# touch-24-v4.net
KiCad netlist of a schematic drawn in Altium Designer
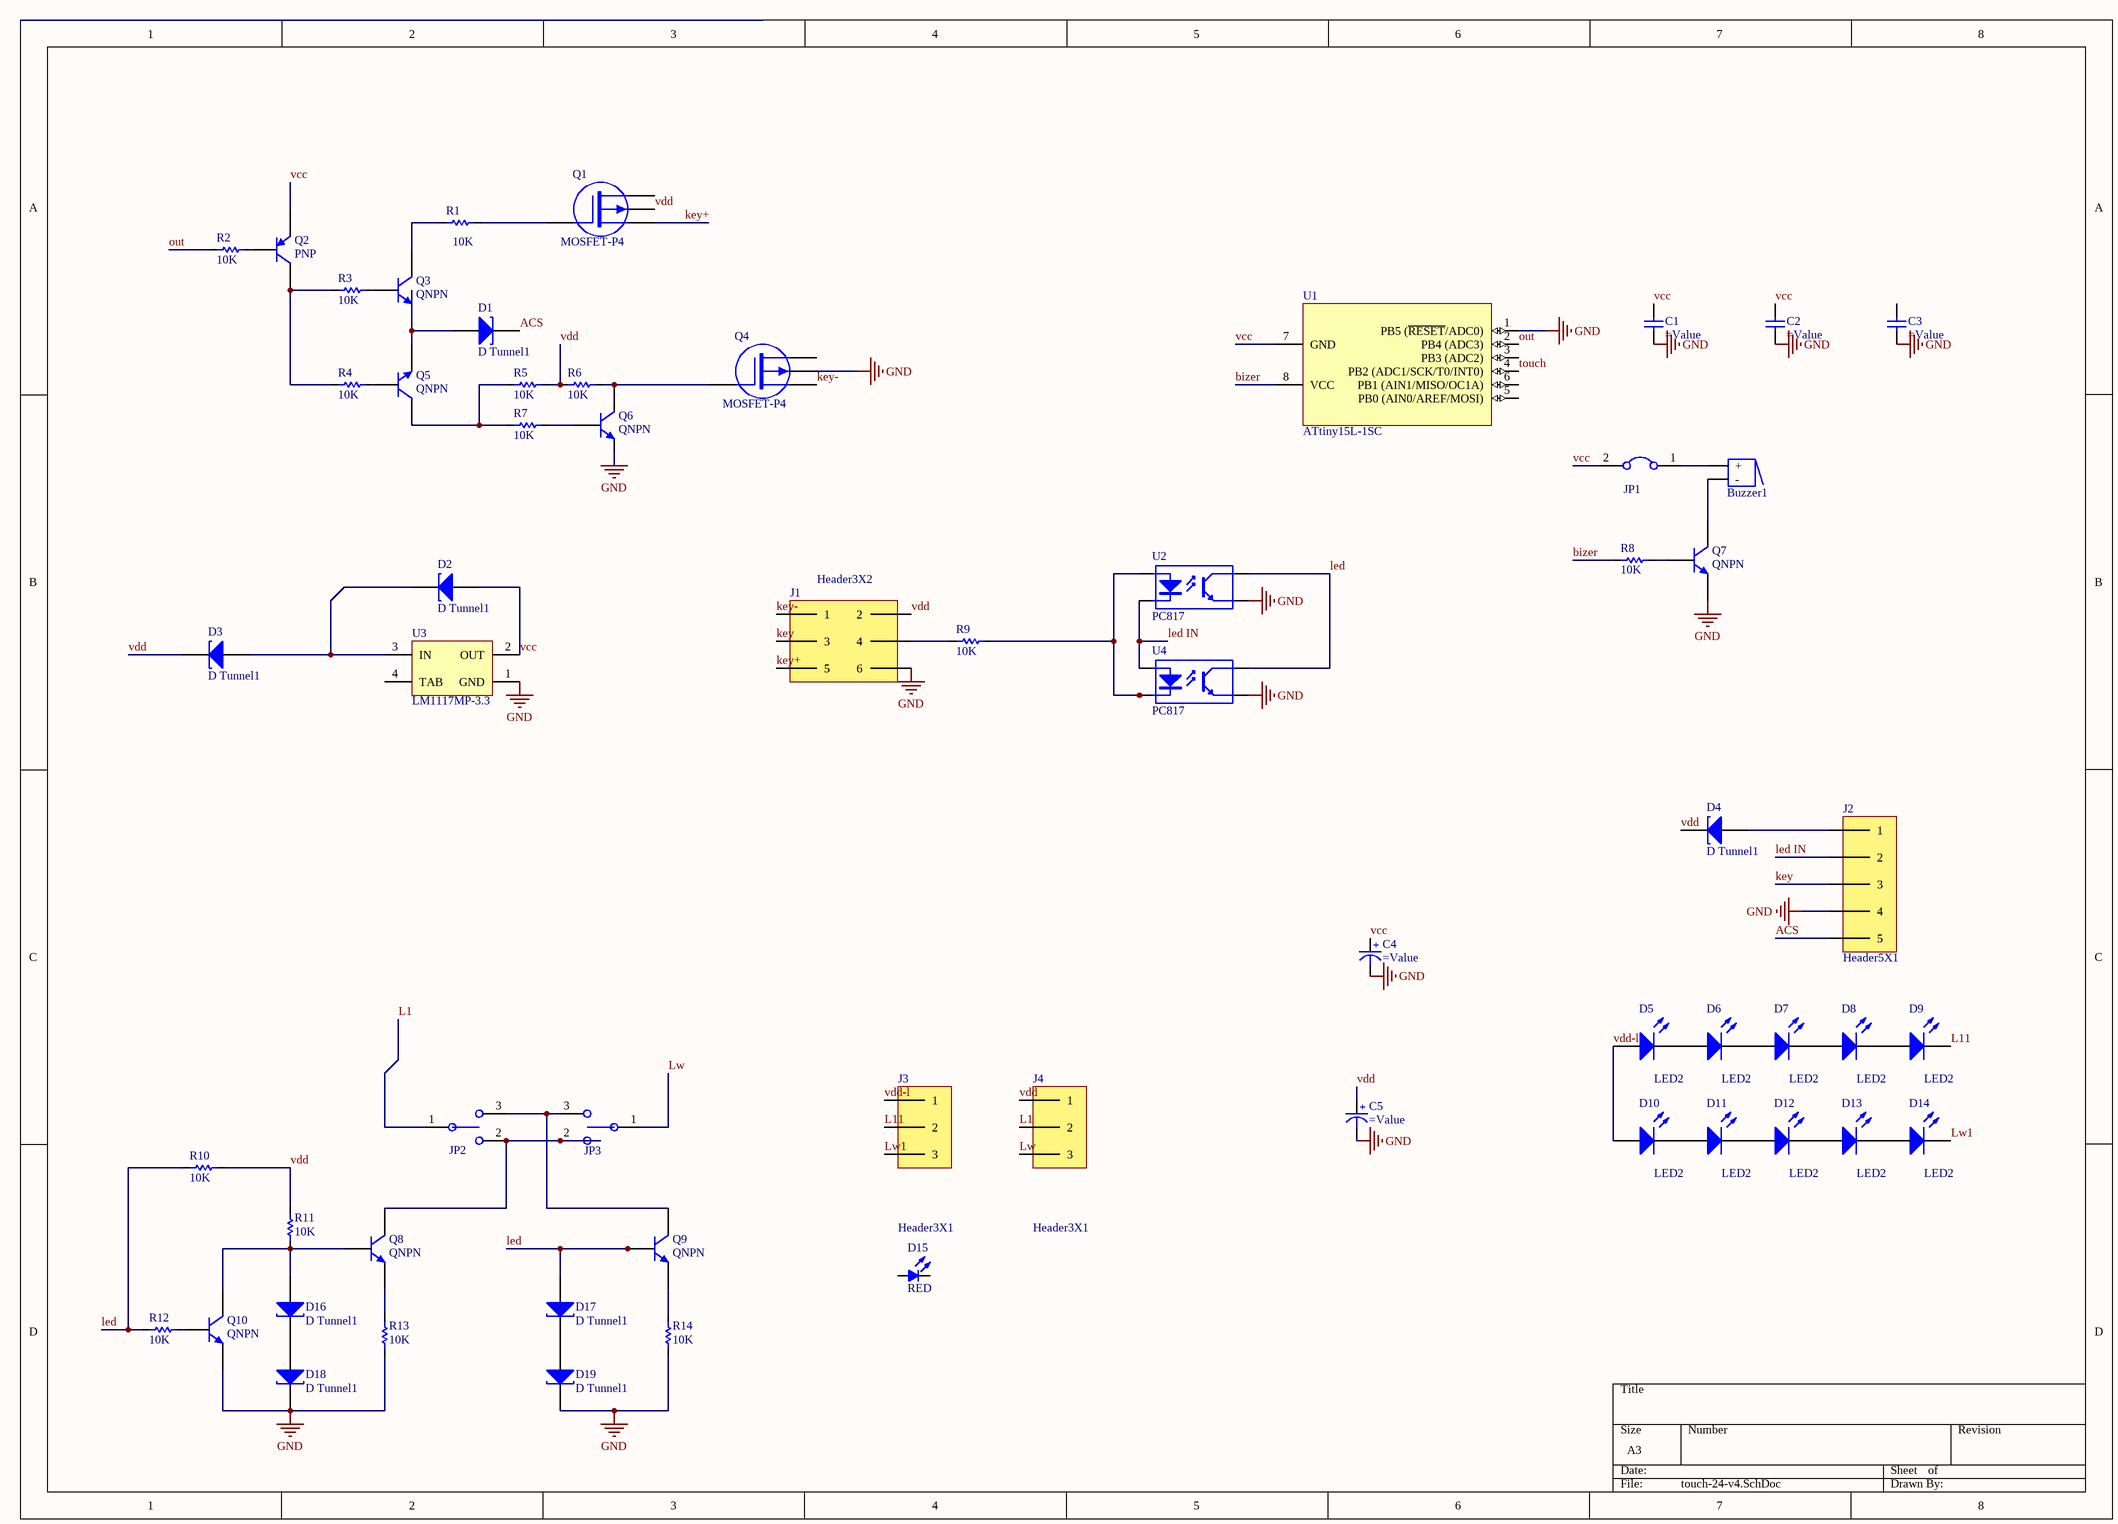
[diagram p0: touch-24-v4.SchDoc]

(export (version "E")
  (design (tool "Eeschema 10.0.6"))
  (components
    (comp (ref "Buzzer1")
      (value "Buzzer")
      (footprint "BUZZER")
      (fields (field (name "DESIGNER") "Seyed Mohsen Ghasemain"))
      (libsource (lib "PicPars.com_usefully_Library") (part "Buzzer"))
    )
    (comp (ref "C1")
      (value "~")
      (footprint "CAP 1206")
      (description "Capacitor")
      (libsource (lib "AltiumLib1") (part "Capacitor"))
    )
    (comp (ref "C2")
      (value "~")
      (footprint "CAP 1206")
      (description "Capacitor")
      (libsource (lib "AltiumLib1") (part "Capacitor"))
    )
    (comp (ref "C3")
      (value "~")
      (footprint "CAP 1206")
      (description "Capacitor")
      (libsource (lib "AltiumLib1") (part "Capacitor"))
    )
    (comp (ref "C4")
      (value "~")
      (footprint "ELEC-CAP-RAD10-20")
      (description "Electrolytic Capacitor")
      (libsource (lib "AltiumLib1") (part "Capacitor Electrolytic"))
    )
    (comp (ref "C5")
      (value "~")
      (footprint "ELEC-CAP-RAD15-30")
      (description "Electrolytic Capacitor")
      (libsource (lib "AltiumLib1") (part "Capacitor Electrolytic"))
    )
    (comp (ref "D1")
      (value "D Tunnel1")
      (footprint "3.2X1.6X1.1")
      (description "Tunnel Diode - RLC Model")
      (fields (field (name "PUBLISHER") "Altium Limited"))
      (libsource (lib "Miscellaneous Devices") (part "D Tunnel1"))
    )
    (comp (ref "D2")
      (value "D Tunnel1")
      (footprint "3.2X1.6X1.1")
      (description "Tunnel Diode - RLC Model")
      (fields (field (name "PUBLISHER") "Altium Limited"))
      (libsource (lib "Miscellaneous Devices") (part "D Tunnel1"))
    )
    (comp (ref "D3")
      (value "D Tunnel1")
      (footprint "3.2X1.6X1.1")
      (description "Tunnel Diode - RLC Model")
      (fields (field (name "PUBLISHER") "Altium Limited"))
      (libsource (lib "Miscellaneous Devices") (part "D Tunnel1"))
    )
    (comp (ref "D4")
      (value "D Tunnel1")
      (footprint "3.2X1.6X1.1")
      (description "Tunnel Diode - RLC Model")
      (fields (field (name "PUBLISHER") "Altium Limited"))
      (libsource (lib "Miscellaneous Devices") (part "D Tunnel1"))
    )
    (comp (ref "D5")
      (value "LED2")
      (footprint "3.2X1.6X1.1")
      (description "Typical RED, GREEN, YELLOW, AMBER GaAs LED")
      (fields (field (name "PUBLISHER") "Altium Limited"))
      (libsource (lib "Miscellaneous Devices") (part "LED2"))
    )
    (comp (ref "D6")
      (value "LED2")
      (footprint "3.2X1.6X1.1")
      (description "Typical RED, GREEN, YELLOW, AMBER GaAs LED")
      (fields (field (name "PUBLISHER") "Altium Limited"))
      (libsource (lib "Miscellaneous Devices") (part "LED2"))
    )
    (comp (ref "D7")
      (value "LED2")
      (footprint "3.2X1.6X1.1")
      (description "Typical RED, GREEN, YELLOW, AMBER GaAs LED")
      (fields (field (name "PUBLISHER") "Altium Limited"))
      (libsource (lib "Miscellaneous Devices") (part "LED2"))
    )
    (comp (ref "D8")
      (value "LED2")
      (footprint "3.2X1.6X1.1")
      (description "Typical RED, GREEN, YELLOW, AMBER GaAs LED")
      (fields (field (name "PUBLISHER") "Altium Limited"))
      (libsource (lib "Miscellaneous Devices") (part "LED2"))
    )
    (comp (ref "D9")
      (value "LED2")
      (footprint "3.2X1.6X1.1")
      (description "Typical RED, GREEN, YELLOW, AMBER GaAs LED")
      (fields (field (name "PUBLISHER") "Altium Limited"))
      (libsource (lib "Miscellaneous Devices") (part "LED2"))
    )
    (comp (ref "D10")
      (value "LED2")
      (footprint "3.2X1.6X1.1")
      (description "Typical RED, GREEN, YELLOW, AMBER GaAs LED")
      (fields (field (name "PUBLISHER") "Altium Limited"))
      (libsource (lib "Miscellaneous Devices") (part "LED2"))
    )
    (comp (ref "D11")
      (value "LED2")
      (footprint "3.2X1.6X1.1")
      (description "Typical RED, GREEN, YELLOW, AMBER GaAs LED")
      (fields (field (name "PUBLISHER") "Altium Limited"))
      (libsource (lib "Miscellaneous Devices") (part "LED2"))
    )
    (comp (ref "D12")
      (value "LED2")
      (footprint "3.2X1.6X1.1")
      (description "Typical RED, GREEN, YELLOW, AMBER GaAs LED")
      (fields (field (name "PUBLISHER") "Altium Limited"))
      (libsource (lib "Miscellaneous Devices") (part "LED2"))
    )
    (comp (ref "D13")
      (value "LED2")
      (footprint "3.2X1.6X1.1")
      (description "Typical RED, GREEN, YELLOW, AMBER GaAs LED")
      (fields (field (name "PUBLISHER") "Altium Limited"))
      (libsource (lib "Miscellaneous Devices") (part "LED2"))
    )
    (comp (ref "D14")
      (value "LED2")
      (footprint "3.2X1.6X1.1")
      (description "Typical RED, GREEN, YELLOW, AMBER GaAs LED")
      (fields (field (name "PUBLISHER") "Altium Limited"))
      (libsource (lib "Miscellaneous Devices") (part "LED2"))
    )
    (comp (ref "D15")
      (value "MODEL")
      (footprint "RES 0805 (2012X06L)")
      (description "Typical LED")
      (fields (field (name "COLOR") "RED"))
      (libsource (lib "AltiumLib1") (part "LED 5mm"))
    )
    (comp (ref "D16")
      (value "D Tunnel1")
      (footprint "3.2X1.6X1.1")
      (description "Tunnel Diode - RLC Model")
      (fields (field (name "PUBLISHER") "Altium Limited"))
      (libsource (lib "Miscellaneous Devices") (part "D Tunnel1"))
    )
    (comp (ref "D17")
      (value "D Tunnel1")
      (footprint "3.2X1.6X1.1")
      (description "Tunnel Diode - RLC Model")
      (fields (field (name "PUBLISHER") "Altium Limited"))
      (libsource (lib "Miscellaneous Devices") (part "D Tunnel1"))
    )
    (comp (ref "D18")
      (value "D Tunnel1")
      (footprint "3.2X1.6X1.1")
      (description "Tunnel Diode - RLC Model")
      (fields (field (name "PUBLISHER") "Altium Limited"))
      (libsource (lib "Miscellaneous Devices") (part "D Tunnel1"))
    )
    (comp (ref "D19")
      (value "D Tunnel1")
      (footprint "3.2X1.6X1.1")
      (description "Tunnel Diode - RLC Model")
      (fields (field (name "PUBLISHER") "Altium Limited"))
      (libsource (lib "Miscellaneous Devices") (part "D Tunnel1"))
    )
    (comp (ref "J1")
      (value "Header3X2")
      (footprint "HEADER 3X2")
      (libsource (lib "AltiumLib1") (part "Header3X2"))
    )
    (comp (ref "J2")
      (value "Header5X1")
      (footprint "HEADER 5X1")
      (libsource (lib "AltiumLib1") (part "Header5X1"))
    )
    (comp (ref "J3")
      (value "Header3X1")
      (footprint "HEADER 3X1")
      (libsource (lib "AltiumLib1") (part "Header3X1"))
    )
    (comp (ref "J4")
      (value "Header3X1")
      (footprint "HEADER 3X1")
      (libsource (lib "AltiumLib1") (part "Header3X1"))
    )
    (comp (ref "JP1")
      (value "Jumper")
      (footprint "Header 2X1")
      (libsource (lib "AltiumLib1") (part "Jumper"))
    )
    (comp (ref "JP2")
      (value "Jumper Selector")
      (footprint "Jumper Selector")
      (libsource (lib "") (part "Jumper Selector_1"))
    )
    (comp (ref "JP3")
      (value "Jumper Selector")
      (footprint "Jumper Selector")
      (libsource (lib "AltiumLib1") (part "Jumper Selector"))
    )
    (comp (ref "Q1")
      (value "MOSFET-P4")
      (footprint "SOT223_N")
      (description "P-Channel MOSFET, Externally Terminated Substrate")
      (fields (field (name "PUBLISHER") "Altium Limited"))
      (libsource (lib "Miscellaneous Devices") (part "MOSFET-P4"))
    )
    (comp (ref "Q2")
      (value "PNP")
      (footprint "SOT-23B_N")
      (description "PNP Bipolar Transistor")
      (fields (field (name "PUBLISHER") "Altium Limited"))
      (libsource (lib "Miscellaneous Devices") (part "PNP"))
    )
    (comp (ref "Q3")
      (value "QNPN")
      (footprint "SOT-23B_L")
      (description "NPN Bipolar Transistor")
      (fields (field (name "PUBLISHER") "Altium Limited"))
      (libsource (lib "Miscellaneous Devices") (part "QNPN"))
    )
    (comp (ref "Q4")
      (value "MOSFET-P4")
      (footprint "SOT223_N")
      (description "P-Channel MOSFET, Externally Terminated Substrate")
      (fields (field (name "PUBLISHER") "Altium Limited"))
      (libsource (lib "Miscellaneous Devices") (part "MOSFET-P4"))
    )
    (comp (ref "Q5")
      (value "QNPN")
      (footprint "SOT-23B_L")
      (description "NPN Bipolar Transistor")
      (fields (field (name "PUBLISHER") "Altium Limited"))
      (libsource (lib "Miscellaneous Devices") (part "QNPN"))
    )
    (comp (ref "Q6")
      (value "QNPN")
      (footprint "SOT-23B_L")
      (description "NPN Bipolar Transistor")
      (fields (field (name "PUBLISHER") "Altium Limited"))
      (libsource (lib "Miscellaneous Devices") (part "QNPN"))
    )
    (comp (ref "Q7")
      (value "QNPN")
      (footprint "SOT-23B_L")
      (description "NPN Bipolar Transistor")
      (fields (field (name "PUBLISHER") "Altium Limited"))
      (libsource (lib "Miscellaneous Devices") (part "QNPN"))
    )
    (comp (ref "Q8")
      (value "QNPN")
      (footprint "SOT-23B_L")
      (description "NPN Bipolar Transistor")
      (fields (field (name "PUBLISHER") "Altium Limited"))
      (libsource (lib "Miscellaneous Devices") (part "QNPN"))
    )
    (comp (ref "Q9")
      (value "QNPN")
      (footprint "SOT-23B_L")
      (description "NPN Bipolar Transistor")
      (fields (field (name "PUBLISHER") "Altium Limited"))
      (libsource (lib "Miscellaneous Devices") (part "QNPN"))
    )
    (comp (ref "Q10")
      (value "QNPN")
      (footprint "SOT-23B_L")
      (description "NPN Bipolar Transistor")
      (fields (field (name "PUBLISHER") "Altium Limited"))
      (libsource (lib "Miscellaneous Devices") (part "QNPN"))
    )
    (comp (ref "R1")
      (value "10K")
      (footprint "RES 1206 (3216X08L)")
      (description "Resistor")
      (fields (field (name "TOLERANCE") "5%") (field (name "POWER") "1/4 W"))
      (libsource (lib "AltiumLib1") (part "Resistor"))
    )
    (comp (ref "R2")
      (value "10K")
      (footprint "RES 1206 (3216X08L)")
      (description "Resistor")
      (fields (field (name "TOLERANCE") "5%") (field (name "POWER") "1/4 W"))
      (libsource (lib "AltiumLib1") (part "Resistor"))
    )
    (comp (ref "R3")
      (value "10K")
      (footprint "RES 1206 (3216X08L)")
      (description "Resistor")
      (fields (field (name "TOLERANCE") "5%") (field (name "POWER") "1/4 W"))
      (libsource (lib "AltiumLib1") (part "Resistor"))
    )
    (comp (ref "R4")
      (value "10K")
      (footprint "RES 1206 (3216X08L)")
      (description "Resistor")
      (fields (field (name "TOLERANCE") "5%") (field (name "POWER") "1/4 W"))
      (libsource (lib "AltiumLib1") (part "Resistor"))
    )
    (comp (ref "R5")
      (value "10K")
      (footprint "RES 1206 (3216X08L)")
      (description "Resistor")
      (fields (field (name "TOLERANCE") "5%") (field (name "POWER") "1/4 W"))
      (libsource (lib "AltiumLib1") (part "Resistor"))
    )
    (comp (ref "R6")
      (value "10K")
      (footprint "RES 1206 (3216X08L)")
      (description "Resistor")
      (fields (field (name "TOLERANCE") "5%") (field (name "POWER") "1/4 W"))
      (libsource (lib "AltiumLib1") (part "Resistor"))
    )
    (comp (ref "R7")
      (value "10K")
      (footprint "RES 1206 (3216X08L)")
      (description "Resistor")
      (fields (field (name "TOLERANCE") "5%") (field (name "POWER") "1/4 W"))
      (libsource (lib "AltiumLib1") (part "Resistor"))
    )
    (comp (ref "R8")
      (value "10K")
      (footprint "RES 1206 (3216X08L)")
      (description "Resistor")
      (fields (field (name "TOLERANCE") "5%") (field (name "POWER") "1/4 W"))
      (libsource (lib "AltiumLib1") (part "Resistor"))
    )
    (comp (ref "R9")
      (value "10K")
      (footprint "RES 1206 (3216X08L)")
      (description "Resistor")
      (fields (field (name "TOLERANCE") "5%") (field (name "POWER") "1/4 W"))
      (libsource (lib "AltiumLib1") (part "Resistor"))
    )
    (comp (ref "R10")
      (value "10K")
      (footprint "RES 1206 (3216X08L)")
      (description "Resistor")
      (fields (field (name "TOLERANCE") "5%") (field (name "POWER") "1/4 W"))
      (libsource (lib "AltiumLib1") (part "Resistor"))
    )
    (comp (ref "R11")
      (value "10K")
      (footprint "RES 1206 (3216X08L)")
      (description "Resistor")
      (fields (field (name "TOLERANCE") "5%") (field (name "POWER") "1/4 W"))
      (libsource (lib "AltiumLib1") (part "Resistor"))
    )
    (comp (ref "R12")
      (value "10K")
      (footprint "RES 1206 (3216X08L)")
      (description "Resistor")
      (fields (field (name "TOLERANCE") "5%") (field (name "POWER") "1/4 W"))
      (libsource (lib "AltiumLib1") (part "Resistor"))
    )
    (comp (ref "R13")
      (value "10K")
      (footprint "RES 1206 (3216X08L)")
      (description "Resistor")
      (fields (field (name "TOLERANCE") "5%") (field (name "POWER") "1/4 W"))
      (libsource (lib "AltiumLib1") (part "Resistor"))
    )
    (comp (ref "R14")
      (value "10K")
      (footprint "RES 1206 (3216X08L)")
      (description "Resistor")
      (fields (field (name "TOLERANCE") "5%") (field (name "POWER") "1/4 W"))
      (libsource (lib "AltiumLib1") (part "Resistor"))
    )
    (comp (ref "U1")
      (value "ATtiny15L-1SC")
      (footprint "8S2_N")
      (description "8-Bit AVR Microcontroller with 1K Byte of Flash Memory")
      (fields (field (name "PUBLISHER") "Altium Limited"))
      (libsource (lib "Atmel Microcontroller 8-Bit AVR") (part "ATtiny15L-1SC"))
    )
    (comp (ref "U2")
      (value "PC817")
      (footprint "DIP4")
      (description "4-Pin Phototransistor Optocoupler")
      (libsource (lib "AltiumLib1") (part "OPTCOUPLER_01"))
    )
    (comp (ref "U3")
      (value "LM1117MP-3.3")
      (footprint "Miscellaneous Devices:SOT89L")
      (description "800mA Low-Dropout Linear Regulator")
      (fields
        (field (name "MANUFACTURER") "National Semiconductor")
        (field (name "DIGIKEYPARTNUMBER") "LM1117MP-3.3CT-ND")
        (field (name "PUBLISHER") "Altium Limited")
      )
      (libsource (lib "NSC LDO") (part "LM1117MP-3.3"))
    )
    (comp (ref "U4")
      (value "PC817")
      (footprint "DIP4")
      (description "4-Pin Phototransistor Optocoupler")
      (libsource (lib "AltiumLib1") (part "OPTCOUPLER_01"))
    )
  )
  (nets
    (net (code "1") (name "/ACS") (class "Default")
      (node (ref "D1") (pin "2") (pinfunction "K_2") (pintype "passive"))
      (node (ref "J2") (pin "5") (pinfunction "5_5") (pintype "passive"))
    )
    (net (code "2") (name "/L1") (class "Default")
      (node (ref "J4") (pin "2") (pinfunction "2_2") (pintype "passive"))
      (node (ref "JP2") (pin "1") (pinfunction "1_1") (pintype "passive"))
    )
    (net (code "3") (name "/L11") (class "Default")
      (node (ref "D9") (pin "2") (pinfunction "K_2") (pintype "passive"))
      (node (ref "J3") (pin "2") (pinfunction "2_2") (pintype "passive"))
    )
    (net (code "4") (name "/Lw") (class "Default")
      (node (ref "J4") (pin "3") (pinfunction "3_3") (pintype "passive"))
      (node (ref "JP3") (pin "1") (pinfunction "1_1") (pintype "passive"))
    )
    (net (code "5") (name "/Lw1") (class "Default")
      (node (ref "D14") (pin "2") (pinfunction "K_2") (pintype "passive"))
      (node (ref "J3") (pin "3") (pinfunction "3_3") (pintype "passive"))
    )
    (net (code "6") (name "/bizer") (class "Default")
      (node (ref "R8") (pin "1") (pinfunction "1_1") (pintype "passive"))
      (node (ref "U1") (pin "8") (pinfunction "VCC_8") (pintype "power_in"))
    )
    (net (code "7") (name "/key") (class "Default")
      (node (ref "J1") (pin "3") (pinfunction "3_3") (pintype "passive"))
      (node (ref "J2") (pin "3") (pinfunction "3_3") (pintype "passive"))
    )
    (net (code "8") (name "/key+") (class "Default")
      (node (ref "J1") (pin "5") (pinfunction "5_5") (pintype "passive"))
      (node (ref "Q1") (pin "4") (pinfunction "S_4") (pintype "passive"))
    )
    (net (code "9") (name "/key-") (class "Default")
      (node (ref "J1") (pin "1") (pinfunction "1_1") (pintype "passive"))
      (node (ref "Q4") (pin "4") (pinfunction "S_4") (pintype "passive"))
    )
    (net (code "10") (name "/led") (class "Default")
      (node (ref "D17") (pin "1") (pinfunction "A_1") (pintype "passive"))
      (node (ref "Q9") (pin "2") (pinfunction "B_2") (pintype "passive"))
      (node (ref "R10") (pin "1") (pinfunction "1_1") (pintype "passive"))
      (node (ref "R12") (pin "1") (pinfunction "1_1") (pintype "passive"))
      (node (ref "U2") (pin "4") (pinfunction "C_4") (pintype "passive"))
      (node (ref "U4") (pin "4") (pinfunction "C_4") (pintype "passive"))
    )
    (net (code "11") (name "/led IN") (class "Default")
      (node (ref "J2") (pin "2") (pinfunction "2_2") (pintype "passive"))
      (node (ref "U2") (pin "2") (pinfunction "K_2") (pintype "passive"))
      (node (ref "U4") (pin "1") (pinfunction "A_1") (pintype "passive"))
    )
    (net (code "12") (name "/out") (class "Default")
      (node (ref "R2") (pin "1") (pinfunction "1_1") (pintype "passive"))
      (node (ref "U1") (pin "2") (pinfunction "PB4_(ADC3)_2") (pintype "bidirectional"))
    )
    (net (code "13") (name "/touch") (class "Default")
      (node (ref "U1") (pin "4") (pinfunction "PB2_(ADC1/SCK/T0/INT0)_4") (pintype "bidirectional"))
    )
    (net (code "14") (name "/vcc") (class "Default")
      (node (ref "C1") (pin "2") (pinfunction "-_2") (pintype "passive"))
      (node (ref "C2") (pin "2") (pinfunction "-_2") (pintype "passive"))
      (node (ref "C4") (pin "2") (pinfunction "+_2") (pintype "passive"))
      (node (ref "D2") (pin "1") (pinfunction "A_1") (pintype "passive"))
      (node (ref "JP1") (pin "2") (pinfunction "2_2") (pintype "passive"))
      (node (ref "Q2") (pin "3") (pinfunction "E_3") (pintype "passive"))
      (node (ref "U1") (pin "7") (pinfunction "GND_7") (pintype "power_in"))
      (node (ref "U3") (pin "2") (pinfunction "OUT_2") (pintype "power_in"))
    )
    (net (code "15") (name "/vdd") (class "Default")
      (node (ref "C5") (pin "2") (pinfunction "+_2") (pintype "passive"))
      (node (ref "D3") (pin "2") (pinfunction "K_2") (pintype "passive"))
      (node (ref "D4") (pin "2") (pinfunction "K_2") (pintype "passive"))
      (node (ref "J1") (pin "2") (pinfunction "2_2") (pintype "passive"))
      (node (ref "J4") (pin "1") (pinfunction "1_1") (pintype "passive"))
      (node (ref "Q1") (pin "3") (pinfunction "U_3") (pintype "passive"))
      (node (ref "R10") (pin "2") (pinfunction "2_2") (pintype "passive"))
      (node (ref "R11") (pin "2") (pinfunction "2_2") (pintype "passive"))
      (node (ref "R5") (pin "2") (pinfunction "2_2") (pintype "passive"))
      (node (ref "R6") (pin "1") (pinfunction "1_1") (pintype "passive"))
    )
    (net (code "16") (name "/vdd-l") (class "Default")
      (node (ref "D10") (pin "1") (pinfunction "A_1") (pintype "passive"))
      (node (ref "D5") (pin "1") (pinfunction "A_1") (pintype "passive"))
      (node (ref "J3") (pin "1") (pinfunction "1_1") (pintype "passive"))
    )
    (net (code "17") (name "GND") (class "Default")
      (node (ref "C1") (pin "1") (pinfunction "+_1") (pintype "passive"))
      (node (ref "C2") (pin "1") (pinfunction "+_1") (pintype "passive"))
      (node (ref "C3") (pin "1") (pinfunction "+_1") (pintype "passive"))
      (node (ref "C4") (pin "1") (pinfunction "-_1") (pintype "passive"))
      (node (ref "C5") (pin "1") (pinfunction "-_1") (pintype "passive"))
      (node (ref "D18") (pin "2") (pinfunction "K_2") (pintype "passive"))
      (node (ref "D19") (pin "2") (pinfunction "K_2") (pintype "passive"))
      (node (ref "J1") (pin "6") (pinfunction "6_6") (pintype "passive"))
      (node (ref "J2") (pin "4") (pinfunction "4_4") (pintype "passive"))
      (node (ref "Q10") (pin "3") (pinfunction "E_3") (pintype "passive"))
      (node (ref "Q4") (pin "3") (pinfunction "U_3") (pintype "passive"))
      (node (ref "Q6") (pin "3") (pinfunction "E_3") (pintype "passive"))
      (node (ref "Q7") (pin "3") (pinfunction "E_3") (pintype "passive"))
      (node (ref "R13") (pin "1") (pinfunction "1_1") (pintype "passive"))
      (node (ref "R14") (pin "1") (pinfunction "1_1") (pintype "passive"))
      (node (ref "U1") (pin "1") (pinfunction "PB5_(~{RESET}/ADC0)_1") (pintype "bidirectional"))
      (node (ref "U2") (pin "3") (pinfunction "E_3") (pintype "passive"))
      (node (ref "U3") (pin "1") (pinfunction "GND_1") (pintype "power_in"))
      (node (ref "U4") (pin "3") (pinfunction "E_3") (pintype "passive"))
    )
    (net (code "18") (name "Net-(Buzzer1-+)") (class "Default")
      (node (ref "Buzzer1") (pin "1") (pinfunction "+_1") (pintype "passive"))
      (node (ref "JP1") (pin "1") (pinfunction "1_1") (pintype "passive"))
    )
    (net (code "19") (name "Net-(Buzzer1--)") (class "Default")
      (node (ref "Buzzer1") (pin "2") (pinfunction "-_2") (pintype "passive"))
      (node (ref "Q7") (pin "1") (pinfunction "C_1") (pintype "passive"))
    )
    (net (code "20") (name "Net-(D1-A)") (class "Default")
      (node (ref "D1") (pin "1") (pinfunction "A_1") (pintype "passive"))
      (node (ref "Q3") (pin "3") (pinfunction "E_3") (pintype "passive"))
      (node (ref "Q5") (pin "3") (pinfunction "E_3") (pintype "passive"))
    )
    (net (code "21") (name "Net-(D2-K)") (class "Default")
      (node (ref "D2") (pin "2") (pinfunction "K_2") (pintype "passive"))
      (node (ref "D3") (pin "1") (pinfunction "A_1") (pintype "passive"))
      (node (ref "U3") (pin "3") (pinfunction "IN_3") (pintype "power_in"))
    )
    (net (code "22") (name "Net-(D4-A)") (class "Default")
      (node (ref "D4") (pin "1") (pinfunction "A_1") (pintype "passive"))
      (node (ref "J2") (pin "1") (pinfunction "1_1") (pintype "passive"))
    )
    (net (code "23") (name "Net-(D5-K)") (class "Default")
      (node (ref "D5") (pin "2") (pinfunction "K_2") (pintype "passive"))
      (node (ref "D6") (pin "1") (pinfunction "A_1") (pintype "passive"))
    )
    (net (code "24") (name "Net-(D6-K)") (class "Default")
      (node (ref "D6") (pin "2") (pinfunction "K_2") (pintype "passive"))
      (node (ref "D7") (pin "1") (pinfunction "A_1") (pintype "passive"))
    )
    (net (code "25") (name "Net-(D7-K)") (class "Default")
      (node (ref "D7") (pin "2") (pinfunction "K_2") (pintype "passive"))
      (node (ref "D8") (pin "1") (pinfunction "A_1") (pintype "passive"))
    )
    (net (code "26") (name "Net-(D8-K)") (class "Default")
      (node (ref "D8") (pin "2") (pinfunction "K_2") (pintype "passive"))
      (node (ref "D9") (pin "1") (pinfunction "A_1") (pintype "passive"))
    )
    (net (code "27") (name "Net-(D10-K)") (class "Default")
      (node (ref "D10") (pin "2") (pinfunction "K_2") (pintype "passive"))
      (node (ref "D11") (pin "1") (pinfunction "A_1") (pintype "passive"))
    )
    (net (code "28") (name "Net-(D11-K)") (class "Default")
      (node (ref "D11") (pin "2") (pinfunction "K_2") (pintype "passive"))
      (node (ref "D12") (pin "1") (pinfunction "A_1") (pintype "passive"))
    )
    (net (code "29") (name "Net-(D12-K)") (class "Default")
      (node (ref "D12") (pin "2") (pinfunction "K_2") (pintype "passive"))
      (node (ref "D13") (pin "1") (pinfunction "A_1") (pintype "passive"))
    )
    (net (code "30") (name "Net-(D13-K)") (class "Default")
      (node (ref "D13") (pin "2") (pinfunction "K_2") (pintype "passive"))
      (node (ref "D14") (pin "1") (pinfunction "A_1") (pintype "passive"))
    )
    (net (code "31") (name "Net-(D16-A)") (class "Default")
      (node (ref "D16") (pin "1") (pinfunction "A_1") (pintype "passive"))
      (node (ref "Q10") (pin "1") (pinfunction "C_1") (pintype "passive"))
      (node (ref "Q8") (pin "2") (pinfunction "B_2") (pintype "passive"))
      (node (ref "R11") (pin "1") (pinfunction "1_1") (pintype "passive"))
    )
    (net (code "32") (name "Net-(D16-K)") (class "Default")
      (node (ref "D16") (pin "2") (pinfunction "K_2") (pintype "passive"))
      (node (ref "D18") (pin "1") (pinfunction "A_1") (pintype "passive"))
    )
    (net (code "33") (name "Net-(D17-K)") (class "Default")
      (node (ref "D17") (pin "2") (pinfunction "K_2") (pintype "passive"))
      (node (ref "D19") (pin "1") (pinfunction "A_1") (pintype "passive"))
    )
    (net (code "34") (name "Net-(J1-Pad4)") (class "Default")
      (node (ref "J1") (pin "4") (pinfunction "4_4") (pintype "passive"))
      (node (ref "R9") (pin "1") (pinfunction "1_1") (pintype "passive"))
    )
    (net (code "35") (name "Net-(Q1-G)") (class "Default")
      (node (ref "Q1") (pin "1") (pinfunction "G_1") (pintype "passive"))
      (node (ref "R1") (pin "2") (pinfunction "2_2") (pintype "passive"))
    )
    (net (code "36") (name "Net-(Q2-B)") (class "Default")
      (node (ref "Q2") (pin "2") (pinfunction "B_2") (pintype "passive"))
      (node (ref "R2") (pin "2") (pinfunction "2_2") (pintype "passive"))
    )
    (net (code "37") (name "Net-(Q2-C)") (class "Default")
      (node (ref "Q2") (pin "1") (pinfunction "C_1") (pintype "passive"))
      (node (ref "R3") (pin "1") (pinfunction "1_1") (pintype "passive"))
      (node (ref "R4") (pin "1") (pinfunction "1_1") (pintype "passive"))
    )
    (net (code "38") (name "Net-(Q3-B)") (class "Default")
      (node (ref "Q3") (pin "2") (pinfunction "B_2") (pintype "passive"))
      (node (ref "R3") (pin "2") (pinfunction "2_2") (pintype "passive"))
    )
    (net (code "39") (name "Net-(Q3-C)") (class "Default")
      (node (ref "Q3") (pin "1") (pinfunction "C_1") (pintype "passive"))
      (node (ref "R1") (pin "1") (pinfunction "1_1") (pintype "passive"))
    )
    (net (code "40") (name "Net-(Q4-G)") (class "Default")
      (node (ref "Q4") (pin "1") (pinfunction "G_1") (pintype "passive"))
      (node (ref "Q6") (pin "1") (pinfunction "C_1") (pintype "passive"))
      (node (ref "R6") (pin "2") (pinfunction "2_2") (pintype "passive"))
    )
    (net (code "41") (name "Net-(Q5-B)") (class "Default")
      (node (ref "Q5") (pin "2") (pinfunction "B_2") (pintype "passive"))
      (node (ref "R4") (pin "2") (pinfunction "2_2") (pintype "passive"))
    )
    (net (code "42") (name "Net-(Q5-C)") (class "Default")
      (node (ref "Q5") (pin "1") (pinfunction "C_1") (pintype "passive"))
      (node (ref "R5") (pin "1") (pinfunction "1_1") (pintype "passive"))
      (node (ref "R7") (pin "1") (pinfunction "1_1") (pintype "passive"))
    )
    (net (code "43") (name "Net-(Q6-B)") (class "Default")
      (node (ref "Q6") (pin "2") (pinfunction "B_2") (pintype "passive"))
      (node (ref "R7") (pin "2") (pinfunction "2_2") (pintype "passive"))
    )
    (net (code "44") (name "Net-(Q7-B)") (class "Default")
      (node (ref "Q7") (pin "2") (pinfunction "B_2") (pintype "passive"))
      (node (ref "R8") (pin "2") (pinfunction "2_2") (pintype "passive"))
    )
    (net (code "45") (name "Net-(Q8-C)") (class "Default")
      (node (ref "JP2") (pin "2") (pinfunction "2_2") (pintype "passive"))
      (node (ref "JP3") (pin "2") (pinfunction "2_2") (pintype "passive"))
      (node (ref "Q8") (pin "1") (pinfunction "C_1") (pintype "passive"))
    )
    (net (code "46") (name "Net-(Q8-E)") (class "Default")
      (node (ref "Q8") (pin "3") (pinfunction "E_3") (pintype "passive"))
      (node (ref "R13") (pin "2") (pinfunction "2_2") (pintype "passive"))
    )
    (net (code "47") (name "Net-(Q9-C)") (class "Default")
      (node (ref "JP2") (pin "3") (pinfunction "3_3") (pintype "passive"))
      (node (ref "JP3") (pin "3") (pinfunction "3_3") (pintype "passive"))
      (node (ref "Q9") (pin "1") (pinfunction "C_1") (pintype "passive"))
    )
    (net (code "48") (name "Net-(Q9-E)") (class "Default")
      (node (ref "Q9") (pin "3") (pinfunction "E_3") (pintype "passive"))
      (node (ref "R14") (pin "2") (pinfunction "2_2") (pintype "passive"))
    )
    (net (code "49") (name "Net-(Q10-B)") (class "Default")
      (node (ref "Q10") (pin "2") (pinfunction "B_2") (pintype "passive"))
      (node (ref "R12") (pin "2") (pinfunction "2_2") (pintype "passive"))
    )
    (net (code "50") (name "Net-(U2-A)") (class "Default")
      (node (ref "R9") (pin "2") (pinfunction "2_2") (pintype "passive"))
      (node (ref "U2") (pin "1") (pinfunction "A_1") (pintype "passive"))
      (node (ref "U4") (pin "2") (pinfunction "K_2") (pintype "passive"))
    )
    (net (code "51") (name "unconnected-(C3---Pad2)") (class "Default")
      (node (ref "C3") (pin "2") (pinfunction "-_2") (pintype "passive"))
    )
    (net (code "52") (name "unconnected-(D15-A-Pad1)") (class "Default")
      (node (ref "D15") (pin "1") (pinfunction "A_1") (pintype "passive"))
    )
    (net (code "53") (name "unconnected-(D15-K-Pad2)") (class "Default")
      (node (ref "D15") (pin "2") (pinfunction "K_2") (pintype "passive"))
    )
    (net (code "54") (name "unconnected-(Q1-D-Pad2)") (class "Default")
      (node (ref "Q1") (pin "2") (pinfunction "D_2") (pintype "passive"))
    )
    (net (code "55") (name "unconnected-(Q4-D-Pad2)") (class "Default")
      (node (ref "Q4") (pin "2") (pinfunction "D_2") (pintype "passive"))
    )
    (net (code "56") (name "unconnected-(U1-PB0_(AIN0{slash}AREF{slash}MOSI)-Pad5)") (class "Default")
      (node (ref "U1") (pin "5") (pinfunction "PB0_(AIN0/AREF/MOSI)_5") (pintype "bidirectional"))
    )
    (net (code "57") (name "unconnected-(U1-PB1_(AIN1{slash}MISO{slash}OC1A)-Pad6)") (class "Default")
      (node (ref "U1") (pin "6") (pinfunction "PB1_(AIN1/MISO/OC1A)_6") (pintype "bidirectional"))
    )
    (net (code "58") (name "unconnected-(U1-PB3_(ADC2)-Pad3)") (class "Default")
      (node (ref "U1") (pin "3") (pinfunction "PB3_(ADC2)_3") (pintype "bidirectional"))
    )
    (net (code "59") (name "unconnected-(U3-TAB-Pad4)") (class "Default")
      (node (ref "U3") (pin "4") (pinfunction "TAB_4") (pintype "power_in"))
    )
  )
)
